# mrShark_01_a.net
KiCad netlist of a schematic drawn in EAGLE
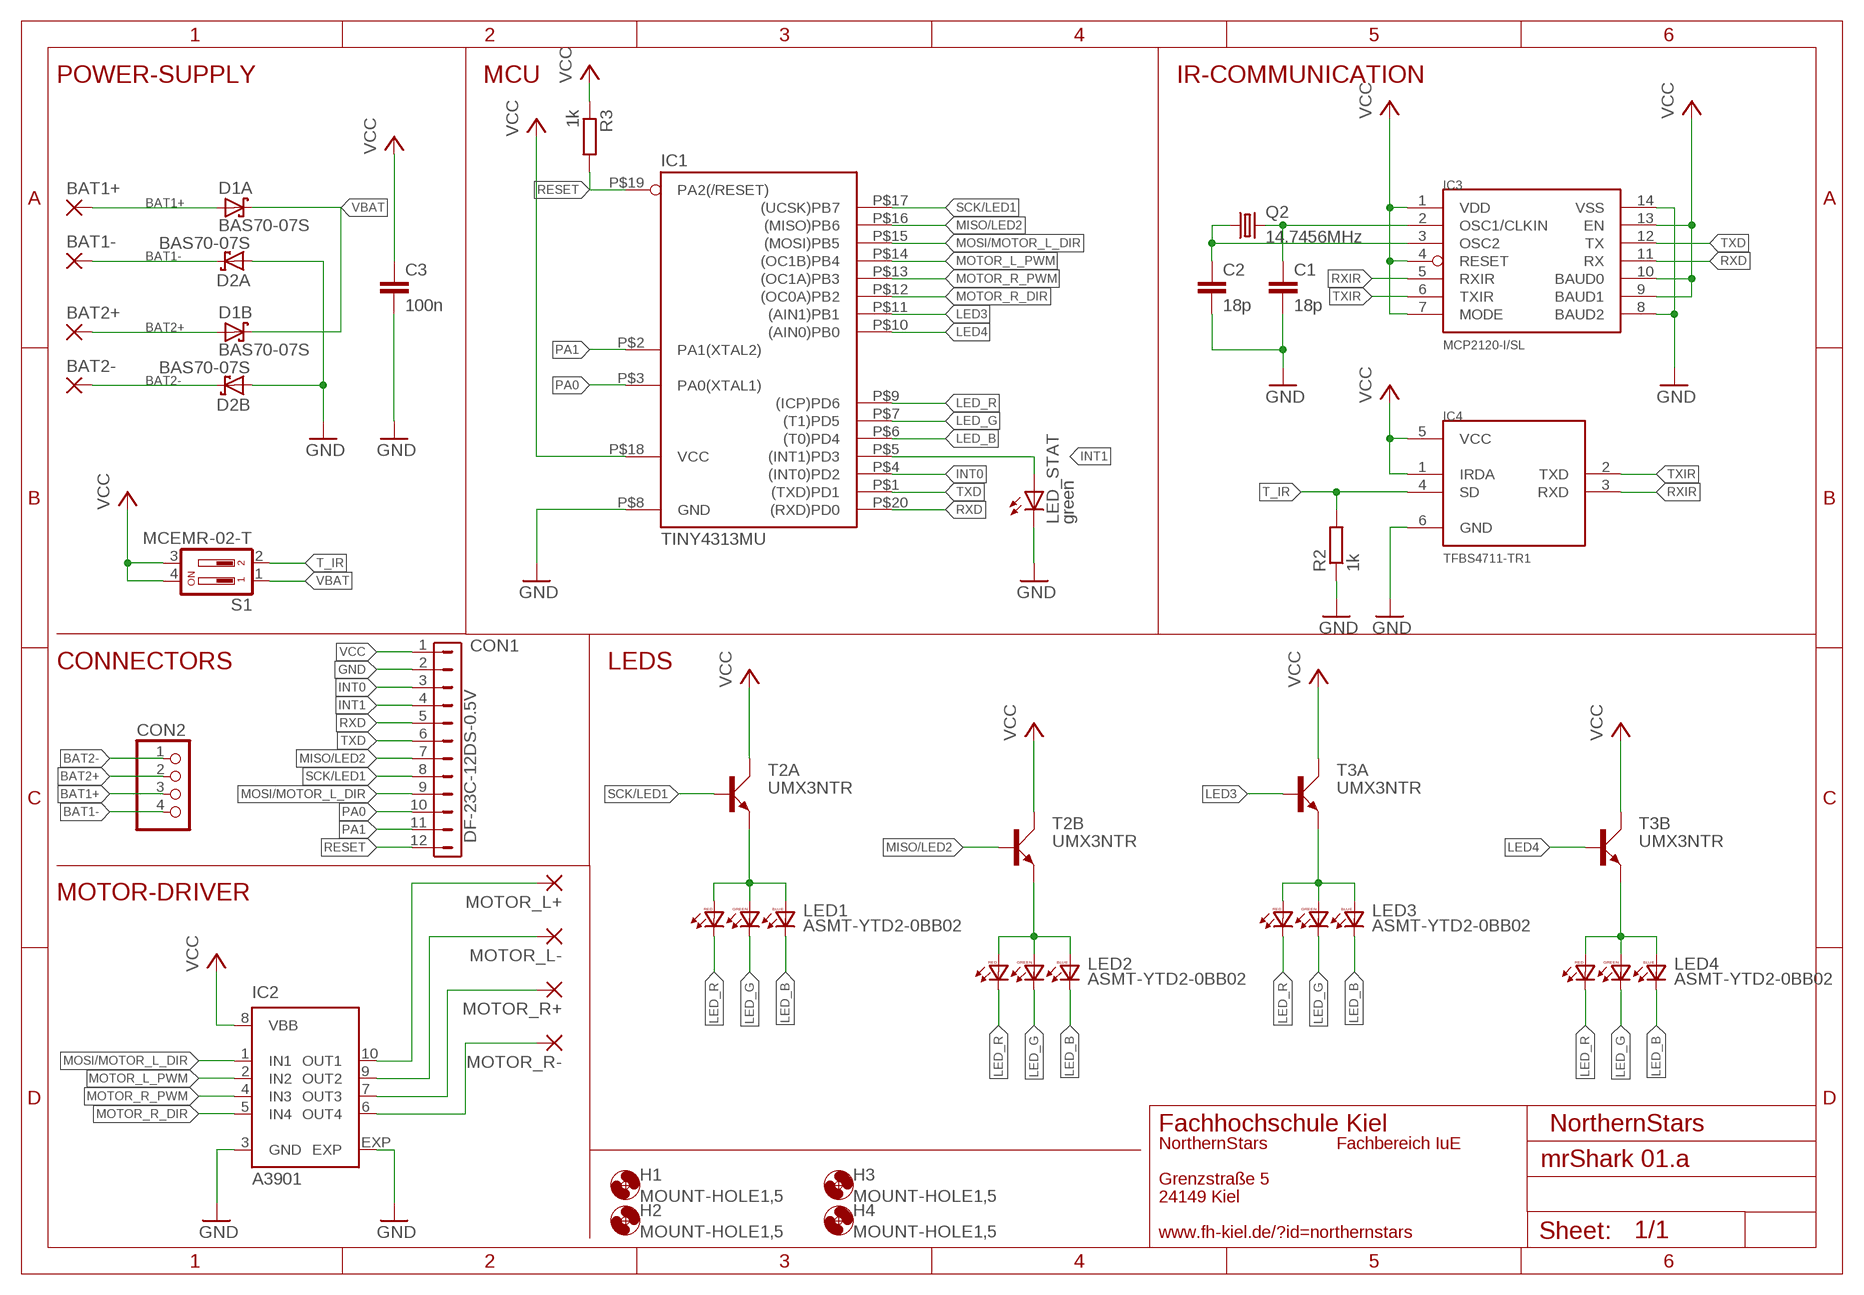
[diagram p0: schematic, sheet 1]

(export (version "E")
  (design (tool "Eeschema 10.0.6"))
  (components
    (comp (ref "BAT1+")
      (value "SMD1")
      (footprint "eagle-import:SMD0,635-1,27")
      (libsource (lib "eagle-import") (part "SMD1"))
    )
    (comp (ref "BAT1-")
      (value "SMD1")
      (footprint "eagle-import:SMD0,635-1,27")
      (libsource (lib "eagle-import") (part "SMD1"))
    )
    (comp (ref "BAT2+")
      (value "SMD1")
      (footprint "eagle-import:SMD0,635-1,27")
      (libsource (lib "eagle-import") (part "SMD1"))
    )
    (comp (ref "BAT2-")
      (value "SMD1")
      (footprint "eagle-import:SMD0,635-1,27")
      (libsource (lib "eagle-import") (part "SMD1"))
    )
    (comp (ref "C1")
      (value "18p")
      (footprint "eagle-import:C0402K")
      (libsource (lib "eagle-import") (part "C-EUC0402K"))
    )
    (comp (ref "C2")
      (value "18p")
      (footprint "eagle-import:C0402K")
      (libsource (lib "eagle-import") (part "C-EUC0402K"))
    )
    (comp (ref "C3")
      (value "100n")
      (footprint "eagle-import:C0402K")
      (libsource (lib "eagle-import") (part "C-EUC0402K"))
    )
    (comp (ref "CON1")
      (value "DF-23C-12DS-0.5V")
      (footprint "eagle-import:DF23C-12DS")
      (libsource (lib "eagle-import") (part "DF-23C-12DS-0.5V"))
    )
    (comp (ref "CON2")
      (value "PINHD-1X04_2.54-S")
      (footprint "eagle-import:1X04-S")
      (libsource (lib "eagle-import") (part "PINHD-1X04_2.54-S"))
    )
    (comp (ref "D1")
      (value "BAS70-07S")
      (footprint "eagle-import:SOT363_PHILIPS")
      (libsource (lib "eagle-import") (part "BAS70-07S"))
    )
    (comp (ref "D2")
      (value "BAS70-07S")
      (footprint "eagle-import:SOT363_PHILIPS")
      (libsource (lib "eagle-import") (part "BAS70-07S"))
    )
    (comp (ref "H1")
      (value "MOUNT-HOLE1,5")
      (footprint "eagle-import:1,5")
      (libsource (lib "eagle-import") (part "MOUNT-HOLE1,5"))
    )
    (comp (ref "H2")
      (value "MOUNT-HOLE1,5")
      (footprint "eagle-import:1,5")
      (libsource (lib "eagle-import") (part "MOUNT-HOLE1,5"))
    )
    (comp (ref "H3")
      (value "MOUNT-HOLE1,5")
      (footprint "eagle-import:1,5")
      (libsource (lib "eagle-import") (part "MOUNT-HOLE1,5"))
    )
    (comp (ref "H4")
      (value "MOUNT-HOLE1,5")
      (footprint "eagle-import:1,5")
      (libsource (lib "eagle-import") (part "MOUNT-HOLE1,5"))
    )
    (comp (ref "IC1")
      (value "TINY4313MU")
      (footprint "eagle-import:MLF20")
      (libsource (lib "eagle-import") (part "TINY4313MU"))
    )
    (comp (ref "IC2")
      (value "A3901")
      (footprint "eagle-import:DFN10-3X3")
      (libsource (lib "eagle-import") (part "A3901"))
    )
    (comp (ref "IC3")
      (value "MCP2120-I/SL")
      (footprint "eagle-import:SO-14")
      (libsource (lib "eagle-import") (part "MCP2120"))
    )
    (comp (ref "IC4")
      (value "TFBS4711-TR1")
      (footprint "eagle-import:TFBS4711")
      (libsource (lib "eagle-import") (part "TFBS4711TR1"))
    )
    (comp (ref "LED1")
      (value "ASMT-YTD2-0BB02")
      (footprint "eagle-import:PLCC6")
      (libsource (lib "eagle-import") (part "PLCC6"))
    )
    (comp (ref "LED2")
      (value "ASMT-YTD2-0BB02")
      (footprint "eagle-import:PLCC6")
      (libsource (lib "eagle-import") (part "PLCC6"))
    )
    (comp (ref "LED3")
      (value "ASMT-YTD2-0BB02")
      (footprint "eagle-import:PLCC6")
      (libsource (lib "eagle-import") (part "PLCC6"))
    )
    (comp (ref "LED4")
      (value "ASMT-YTD2-0BB02")
      (footprint "eagle-import:PLCC6")
      (libsource (lib "eagle-import") (part "PLCC6"))
    )
    (comp (ref "LED_STAT")
      (value "green")
      (footprint "eagle-import:CHIP-LED0603")
      (libsource (lib "eagle-import") (part "LEDCHIP-LED0603"))
    )
    (comp (ref "MOTOR_L+")
      (value "SMD1")
      (footprint "eagle-import:SMD0,635-1,27")
      (libsource (lib "eagle-import") (part "SMD1"))
    )
    (comp (ref "MOTOR_L-")
      (value "SMD1")
      (footprint "eagle-import:SMD0,635-1,27")
      (libsource (lib "eagle-import") (part "SMD1"))
    )
    (comp (ref "MOTOR_R+")
      (value "SMD1")
      (footprint "eagle-import:SMD0,635-1,27")
      (libsource (lib "eagle-import") (part "SMD1"))
    )
    (comp (ref "MOTOR_R-")
      (value "SMD1")
      (footprint "eagle-import:SMD0,635-1,27")
      (libsource (lib "eagle-import") (part "SMD1"))
    )
    (comp (ref "Q2")
      (value "14.7456MHz")
      (footprint "eagle-import:CFPX-104")
      (libsource (lib "eagle-import") (part "CRYSTALCFPX-104"))
    )
    (comp (ref "R2")
      (value "1k")
      (footprint "eagle-import:R0402")
      (libsource (lib "eagle-import") (part "R-EU_R0402"))
    )
    (comp (ref "R3")
      (value "1k")
      (footprint "eagle-import:R0402")
      (libsource (lib "eagle-import") (part "R-EU_R0402"))
    )
    (comp (ref "S1")
      (value "MCEMR-02-T")
      (footprint "eagle-import:CTS-219-02")
      (libsource (lib "eagle-import") (part "219-02"))
    )
    (comp (ref "T2")
      (value "UMX3NTR")
      (footprint "eagle-import:SOT363_INFINEON")
      (libsource (lib "eagle-import") (part "UMX3NTR-SOT363"))
    )
    (comp (ref "T3")
      (value "UMX3NTR")
      (footprint "eagle-import:SOT363_INFINEON")
      (libsource (lib "eagle-import") (part "UMX3NTR-SOT363"))
    )
  )
  (nets
    (net (code "1") (name "BAT1+") (class "Default")
      (node (ref "BAT1+") (pin "P$1") (pinfunction "P_P$1") (pintype "passive"))
      (node (ref "CON2") (pin "3") (pinfunction "3_3") (pintype "passive"))
      (node (ref "D1") (pin "1") (pinfunction "A_1") (pintype "passive"))
    )
    (net (code "2") (name "BAT1-") (class "Default")
      (node (ref "BAT1-") (pin "P$1") (pinfunction "P_P$1") (pintype "passive"))
      (node (ref "CON2") (pin "4") (pinfunction "4_4") (pintype "passive"))
      (node (ref "D2") (pin "6") (pinfunction "C_6") (pintype "passive"))
    )
    (net (code "3") (name "BAT2+") (class "Default")
      (node (ref "BAT2+") (pin "P$1") (pinfunction "P_P$1") (pintype "passive"))
      (node (ref "CON2") (pin "2") (pinfunction "2_2") (pintype "passive"))
      (node (ref "D1") (pin "4") (pinfunction "A_4") (pintype "passive"))
    )
    (net (code "4") (name "BAT2-") (class "Default")
      (node (ref "BAT2-") (pin "P$1") (pinfunction "P_P$1") (pintype "passive"))
      (node (ref "CON2") (pin "1") (pinfunction "1_1") (pintype "passive"))
      (node (ref "D2") (pin "3") (pinfunction "C_3") (pintype "passive"))
    )
    (net (code "5") (name "GND") (class "Default")
      (node (ref "C1") (pin "2") (pinfunction "2_2") (pintype "passive"))
      (node (ref "C2") (pin "2") (pinfunction "2_2") (pintype "passive"))
      (node (ref "C3") (pin "2") (pinfunction "2_2") (pintype "passive"))
      (node (ref "CON1") (pin "2") (pinfunction "2_2") (pintype "passive"))
      (node (ref "D2") (pin "1") (pinfunction "A_1") (pintype "passive"))
      (node (ref "D2") (pin "4") (pinfunction "A_4") (pintype "passive"))
      (node (ref "IC1") (pin "P$8") (pinfunction "GND_P$8") (pintype "power_in"))
      (node (ref "IC2") (pin "3") (pinfunction "GND_3") (pintype "power_in"))
      (node (ref "IC2") (pin "EXP") (pinfunction "EXP_EXP") (pintype "passive"))
      (node (ref "IC3") (pin "14") (pinfunction "VSS_14") (pintype "bidirectional"))
      (node (ref "IC3") (pin "8") (pinfunction "BAUD2_8") (pintype "bidirectional"))
      (node (ref "IC4") (pin "6") (pinfunction "GND_6") (pintype "bidirectional"))
      (node (ref "LED_STAT") (pin "C") (pinfunction "C_C") (pintype "passive"))
      (node (ref "R2") (pin "1") (pinfunction "1_1") (pintype "passive"))
    )
    (net (code "6") (name "INT0") (class "Default")
      (node (ref "CON1") (pin "3") (pinfunction "3_3") (pintype "passive"))
      (node (ref "IC1") (pin "P$4") (pinfunction "(INT0)PD2_P$4") (pintype "bidirectional"))
    )
    (net (code "7") (name "INT1") (class "Default")
      (node (ref "CON1") (pin "4") (pinfunction "4_4") (pintype "passive"))
      (node (ref "IC1") (pin "P$5") (pinfunction "(INT1)PD3_P$5") (pintype "bidirectional"))
      (node (ref "LED_STAT") (pin "A") (pinfunction "A_A") (pintype "passive"))
    )
    (net (code "8") (name "LED3") (class "Default")
      (node (ref "IC1") (pin "P$11") (pinfunction "(AIN1)PB1_P$11") (pintype "bidirectional"))
      (node (ref "T3") (pin "2") (pinfunction "B_2") (pintype "passive"))
    )
    (net (code "9") (name "LED4") (class "Default")
      (node (ref "IC1") (pin "P$10") (pinfunction "(AIN0)PB0_P$10") (pintype "bidirectional"))
      (node (ref "T3") (pin "3") (pinfunction "B_3") (pintype "passive"))
    )
    (net (code "10") (name "LED_B") (class "Default")
      (node (ref "IC1") (pin "P$6") (pinfunction "(T0)PD4_P$6") (pintype "bidirectional"))
      (node (ref "LED1") (pin "1") (pinfunction "BC_1") (pintype "passive"))
      (node (ref "LED2") (pin "1") (pinfunction "BC_1") (pintype "passive"))
      (node (ref "LED3") (pin "1") (pinfunction "BC_1") (pintype "passive"))
      (node (ref "LED4") (pin "1") (pinfunction "BC_1") (pintype "passive"))
    )
    (net (code "11") (name "LED_G") (class "Default")
      (node (ref "IC1") (pin "P$7") (pinfunction "(T1)PD5_P$7") (pintype "bidirectional"))
      (node (ref "LED1") (pin "2") (pinfunction "GC_2") (pintype "passive"))
      (node (ref "LED2") (pin "2") (pinfunction "GC_2") (pintype "passive"))
      (node (ref "LED3") (pin "2") (pinfunction "GC_2") (pintype "passive"))
      (node (ref "LED4") (pin "2") (pinfunction "GC_2") (pintype "passive"))
    )
    (net (code "12") (name "LED_R") (class "Default")
      (node (ref "IC1") (pin "P$9") (pinfunction "(ICP)PD6_P$9") (pintype "bidirectional"))
      (node (ref "LED1") (pin "3") (pinfunction "RC_3") (pintype "passive"))
      (node (ref "LED2") (pin "3") (pinfunction "RC_3") (pintype "passive"))
      (node (ref "LED3") (pin "3") (pinfunction "RC_3") (pintype "passive"))
      (node (ref "LED4") (pin "3") (pinfunction "RC_3") (pintype "passive"))
    )
    (net (code "13") (name "MISO{slash}LED2") (class "Default")
      (node (ref "CON1") (pin "7") (pinfunction "7_7") (pintype "passive"))
      (node (ref "IC1") (pin "P$16") (pinfunction "(MISO)PB6_P$16") (pintype "bidirectional"))
      (node (ref "T2") (pin "3") (pinfunction "B_3") (pintype "passive"))
    )
    (net (code "14") (name "MOSI{slash}MOTOR_L_DIR") (class "Default")
      (node (ref "CON1") (pin "9") (pinfunction "9_9") (pintype "passive"))
      (node (ref "IC1") (pin "P$15") (pinfunction "(MOSI)PB5_P$15") (pintype "bidirectional"))
      (node (ref "IC2") (pin "1") (pinfunction "IN1_1") (pintype "input"))
    )
    (net (code "15") (name "MOTOR_L_PWM") (class "Default")
      (node (ref "IC1") (pin "P$14") (pinfunction "(OC1B)PB4_P$14") (pintype "bidirectional"))
      (node (ref "IC2") (pin "2") (pinfunction "IN2_2") (pintype "input"))
    )
    (net (code "16") (name "MOTOR_R_DIR") (class "Default")
      (node (ref "IC1") (pin "P$12") (pinfunction "(OC0A)PB2_P$12") (pintype "bidirectional"))
      (node (ref "IC2") (pin "5") (pinfunction "IN4_5") (pintype "input"))
    )
    (net (code "17") (name "MOTOR_R_PWM") (class "Default")
      (node (ref "IC1") (pin "P$13") (pinfunction "(OC1A)PB3_P$13") (pintype "bidirectional"))
      (node (ref "IC2") (pin "4") (pinfunction "IN3_4") (pintype "input"))
    )
    (net (code "18") (name "Net-(IC2-OUT1)") (class "Default")
      (node (ref "IC2") (pin "10") (pinfunction "OUT1_10") (pintype "output"))
      (node (ref "MOTOR_L+") (pin "P$1") (pinfunction "P_P$1") (pintype "passive"))
    )
    (net (code "19") (name "Net-(IC2-OUT2)") (class "Default")
      (node (ref "IC2") (pin "9") (pinfunction "OUT2_9") (pintype "output"))
      (node (ref "MOTOR_L-") (pin "P$1") (pinfunction "P_P$1") (pintype "passive"))
    )
    (net (code "20") (name "Net-(IC2-OUT3)") (class "Default")
      (node (ref "IC2") (pin "7") (pinfunction "OUT3_7") (pintype "output"))
      (node (ref "MOTOR_R+") (pin "P$1") (pinfunction "P_P$1") (pintype "passive"))
    )
    (net (code "21") (name "Net-(IC2-OUT4)") (class "Default")
      (node (ref "IC2") (pin "6") (pinfunction "OUT4_6") (pintype "output"))
      (node (ref "MOTOR_R-") (pin "P$1") (pinfunction "P_P$1") (pintype "passive"))
    )
    (net (code "22") (name "Net-(IC3-OSC1{slash}CLKIN)") (class "Default")
      (node (ref "C1") (pin "1") (pinfunction "1_1") (pintype "passive"))
      (node (ref "IC3") (pin "2") (pinfunction "OSC1/CLKIN_2") (pintype "bidirectional"))
      (node (ref "Q2") (pin "P$2") (pinfunction "2_P$2") (pintype "passive"))
    )
    (net (code "23") (name "Net-(IC3-OSC2)") (class "Default")
      (node (ref "C2") (pin "1") (pinfunction "1_1") (pintype "passive"))
      (node (ref "IC3") (pin "3") (pinfunction "OSC2_3") (pintype "bidirectional"))
      (node (ref "Q2") (pin "P$1") (pinfunction "1_P$1") (pintype "passive"))
    )
    (net (code "24") (name "Net-(LED1-BA)") (class "Default")
      (node (ref "LED1") (pin "4") (pinfunction "RA_4") (pintype "passive"))
      (node (ref "LED1") (pin "5") (pinfunction "GA_5") (pintype "passive"))
      (node (ref "LED1") (pin "6") (pinfunction "BA_6") (pintype "passive"))
      (node (ref "T2") (pin "1") (pinfunction "E_1") (pintype "passive"))
    )
    (net (code "25") (name "Net-(LED2-BA)") (class "Default")
      (node (ref "LED2") (pin "4") (pinfunction "RA_4") (pintype "passive"))
      (node (ref "LED2") (pin "5") (pinfunction "GA_5") (pintype "passive"))
      (node (ref "LED2") (pin "6") (pinfunction "BA_6") (pintype "passive"))
      (node (ref "T2") (pin "5") (pinfunction "E_5") (pintype "passive"))
    )
    (net (code "26") (name "Net-(LED3-BA)") (class "Default")
      (node (ref "LED3") (pin "4") (pinfunction "RA_4") (pintype "passive"))
      (node (ref "LED3") (pin "5") (pinfunction "GA_5") (pintype "passive"))
      (node (ref "LED3") (pin "6") (pinfunction "BA_6") (pintype "passive"))
      (node (ref "T3") (pin "1") (pinfunction "E_1") (pintype "passive"))
    )
    (net (code "27") (name "Net-(LED4-BA)") (class "Default")
      (node (ref "LED4") (pin "4") (pinfunction "RA_4") (pintype "passive"))
      (node (ref "LED4") (pin "5") (pinfunction "GA_5") (pintype "passive"))
      (node (ref "LED4") (pin "6") (pinfunction "BA_6") (pintype "passive"))
      (node (ref "T3") (pin "5") (pinfunction "E_5") (pintype "passive"))
    )
    (net (code "28") (name "PA0") (class "Default")
      (node (ref "CON1") (pin "10") (pinfunction "10_10") (pintype "passive"))
      (node (ref "IC1") (pin "P$3") (pinfunction "PA0(XTAL1)_P$3") (pintype "bidirectional"))
    )
    (net (code "29") (name "PA1") (class "Default")
      (node (ref "CON1") (pin "11") (pinfunction "11_11") (pintype "passive"))
      (node (ref "IC1") (pin "P$2") (pinfunction "PA1(XTAL2)_P$2") (pintype "bidirectional"))
    )
    (net (code "30") (name "RESET") (class "Default")
      (node (ref "CON1") (pin "12") (pinfunction "12_12") (pintype "passive"))
      (node (ref "IC1") (pin "P$19") (pinfunction "PA2(/RESET)_P$19") (pintype "input"))
      (node (ref "R3") (pin "2") (pinfunction "2_2") (pintype "passive"))
    )
    (net (code "31") (name "RXD") (class "Default")
      (node (ref "CON1") (pin "5") (pinfunction "5_5") (pintype "passive"))
      (node (ref "IC1") (pin "P$20") (pinfunction "(RXD)PD0_P$20") (pintype "bidirectional"))
      (node (ref "IC3") (pin "11") (pinfunction "RX_11") (pintype "bidirectional"))
    )
    (net (code "32") (name "RXIR") (class "Default")
      (node (ref "IC3") (pin "5") (pinfunction "RXIR_5") (pintype "bidirectional"))
      (node (ref "IC4") (pin "3") (pinfunction "RXD_3") (pintype "output"))
    )
    (net (code "33") (name "SCK{slash}LED1") (class "Default")
      (node (ref "CON1") (pin "8") (pinfunction "8_8") (pintype "passive"))
      (node (ref "IC1") (pin "P$17") (pinfunction "(UCSK)PB7_P$17") (pintype "bidirectional"))
      (node (ref "T2") (pin "2") (pinfunction "B_2") (pintype "passive"))
    )
    (net (code "34") (name "TXD") (class "Default")
      (node (ref "CON1") (pin "6") (pinfunction "6_6") (pintype "passive"))
      (node (ref "IC1") (pin "P$1") (pinfunction "(TXD)PD1_P$1") (pintype "bidirectional"))
      (node (ref "IC3") (pin "12") (pinfunction "TX_12") (pintype "bidirectional"))
    )
    (net (code "35") (name "TXIR") (class "Default")
      (node (ref "IC3") (pin "6") (pinfunction "TXIR_6") (pintype "bidirectional"))
      (node (ref "IC4") (pin "2") (pinfunction "TXD_2") (pintype "input"))
    )
    (net (code "36") (name "T_IR") (class "Default")
      (node (ref "IC4") (pin "4") (pinfunction "SD_4") (pintype "bidirectional"))
      (node (ref "R2") (pin "2") (pinfunction "2_2") (pintype "passive"))
      (node (ref "S1") (pin "2") (pinfunction "2_2") (pintype "passive"))
    )
    (net (code "37") (name "VBAT") (class "Default")
      (node (ref "D1") (pin "3") (pinfunction "C_3") (pintype "passive"))
      (node (ref "D1") (pin "6") (pinfunction "C_6") (pintype "passive"))
      (node (ref "S1") (pin "1") (pinfunction "1_1") (pintype "passive"))
    )
    (net (code "38") (name "VCC") (class "Default")
      (node (ref "C3") (pin "1") (pinfunction "1_1") (pintype "passive"))
      (node (ref "CON1") (pin "1") (pinfunction "1_1") (pintype "passive"))
      (node (ref "IC1") (pin "P$18") (pinfunction "VCC_P$18") (pintype "power_in"))
      (node (ref "IC2") (pin "8") (pinfunction "VBB_8") (pintype "power_in"))
      (node (ref "IC3") (pin "1") (pinfunction "VDD_1") (pintype "bidirectional"))
      (node (ref "IC3") (pin "10") (pinfunction "BAUD0_10") (pintype "bidirectional"))
      (node (ref "IC3") (pin "13") (pinfunction "EN_13") (pintype "bidirectional"))
      (node (ref "IC3") (pin "4") (pinfunction "RESET_4") (pintype "bidirectional"))
      (node (ref "IC3") (pin "7") (pinfunction "MODE_7") (pintype "bidirectional"))
      (node (ref "IC3") (pin "9") (pinfunction "BAUD1_9") (pintype "bidirectional"))
      (node (ref "IC4") (pin "1") (pinfunction "IRDA_1") (pintype "bidirectional"))
      (node (ref "IC4") (pin "5") (pinfunction "VCC_5") (pintype "power_in"))
      (node (ref "R3") (pin "1") (pinfunction "1_1") (pintype "passive"))
      (node (ref "S1") (pin "3") (pinfunction "3_3") (pintype "passive"))
      (node (ref "S1") (pin "4") (pinfunction "4_4") (pintype "passive"))
      (node (ref "T2") (pin "4") (pinfunction "C_4") (pintype "passive"))
      (node (ref "T2") (pin "6") (pinfunction "C_6") (pintype "passive"))
      (node (ref "T3") (pin "4") (pinfunction "C_4") (pintype "passive"))
      (node (ref "T3") (pin "6") (pinfunction "C_6") (pintype "passive"))
    )
  )
)
